# Multivibrator.net
KiCad netlist of a schematic drawn in Altium Designer
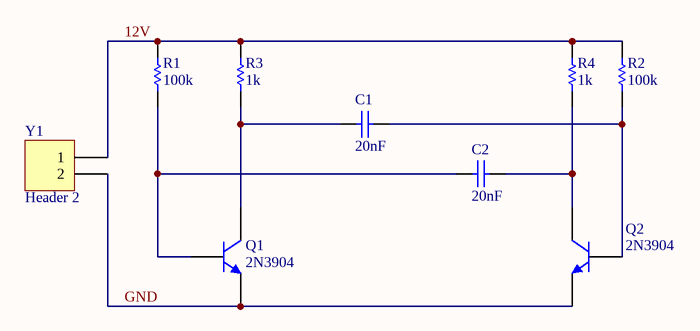
[diagram p0: Multivibrator.SchDoc]

(export (version "E")
  (design (tool "Eeschema 10.0.6"))
  (components
    (comp (ref "C1")
      (value "20nF")
      (footprint "RAD-0.3")
      (description "Capacitor")
      (fields (field (name "PUBLISHER") "Altium Limited"))
      (libsource (lib "Miscellaneous Devices") (part "Cap"))
    )
    (comp (ref "C2")
      (value "20nF")
      (footprint "RAD-0.3")
      (description "Capacitor")
      (fields (field (name "PUBLISHER") "Altium Limited"))
      (libsource (lib "Miscellaneous Devices") (part "Cap"))
    )
    (comp (ref "Q1")
      (value "2N3904")
      (footprint "TO-92A")
      (description "NPN General Purpose Amplifier")
      (fields (field (name "PUBLISHER") "Altium Limited"))
      (libsource (lib "Miscellaneous Devices") (part "2N3904"))
    )
    (comp (ref "Q2")
      (value "2N3904")
      (footprint "TO-92A")
      (description "NPN General Purpose Amplifier")
      (fields (field (name "PUBLISHER") "Altium Limited"))
      (libsource (lib "Miscellaneous Devices") (part "2N3904"))
    )
    (comp (ref "R1")
      (value "100k")
      (footprint "AXIAL-0.3")
      (description "Resistor")
      (fields (field (name "PUBLISHER") "Altium Limited"))
      (libsource (lib "Miscellaneous Devices") (part "Res1"))
    )
    (comp (ref "R2")
      (value "100k")
      (footprint "AXIAL-0.3")
      (description "Resistor")
      (fields (field (name "PUBLISHER") "Altium Limited"))
      (libsource (lib "Miscellaneous Devices") (part "Res1"))
    )
    (comp (ref "R3")
      (value "1k")
      (footprint "AXIAL-0.3")
      (description "Resistor")
      (fields (field (name "PUBLISHER") "Altium Limited"))
      (libsource (lib "Miscellaneous Devices") (part "Res1"))
    )
    (comp (ref "R4")
      (value "1k")
      (footprint "AXIAL-0.3")
      (description "Resistor")
      (fields (field (name "PUBLISHER") "Altium Limited"))
      (libsource (lib "Miscellaneous Devices") (part "Res1"))
    )
    (comp (ref "Y1")
      (value "Header 2")
      (footprint "HDR1X2")
      (description "Header, 2-Pin")
      (fields (field (name "PUBLISHER") "Altium Limited"))
      (libsource (lib "Miscellaneous Connectors") (part "Header 2"))
    )
  )
  (nets
    (net (code "1") (name "/12V") (class "Default")
      (node (ref "R1") (pin "2") (pinfunction "2_2") (pintype "passive"))
      (node (ref "R2") (pin "2") (pinfunction "2_2") (pintype "passive"))
      (node (ref "R3") (pin "2") (pinfunction "2_2") (pintype "passive"))
      (node (ref "R4") (pin "2") (pinfunction "2_2") (pintype "passive"))
      (node (ref "Y1") (pin "1") (pinfunction "1_1") (pintype "passive"))
    )
    (net (code "2") (name "/GND") (class "Default")
      (node (ref "Q1") (pin "1") (pinfunction "E_1") (pintype "passive"))
      (node (ref "Q2") (pin "1") (pinfunction "E_1") (pintype "passive"))
      (node (ref "Y1") (pin "2") (pinfunction "2_2") (pintype "passive"))
    )
    (net (code "3") (name "Net-(Q1-B)") (class "Default")
      (node (ref "C2") (pin "1") (pinfunction "1_1") (pintype "passive"))
      (node (ref "Q1") (pin "2") (pinfunction "B_2") (pintype "passive"))
      (node (ref "R1") (pin "1") (pinfunction "1_1") (pintype "passive"))
    )
    (net (code "4") (name "Net-(Q1-C)") (class "Default")
      (node (ref "C1") (pin "1") (pinfunction "1_1") (pintype "passive"))
      (node (ref "Q1") (pin "3") (pinfunction "C_3") (pintype "passive"))
      (node (ref "R3") (pin "1") (pinfunction "1_1") (pintype "passive"))
    )
    (net (code "5") (name "Net-(Q2-B)") (class "Default")
      (node (ref "C1") (pin "2") (pinfunction "2_2") (pintype "passive"))
      (node (ref "Q2") (pin "2") (pinfunction "B_2") (pintype "passive"))
      (node (ref "R2") (pin "1") (pinfunction "1_1") (pintype "passive"))
    )
    (net (code "6") (name "Net-(Q2-C)") (class "Default")
      (node (ref "C2") (pin "2") (pinfunction "2_2") (pintype "passive"))
      (node (ref "Q2") (pin "3") (pinfunction "C_3") (pintype "passive"))
      (node (ref "R4") (pin "1") (pinfunction "1_1") (pintype "passive"))
    )
  )
)
